# GPRS.net
KiCad netlist of a schematic drawn in Altium Designer
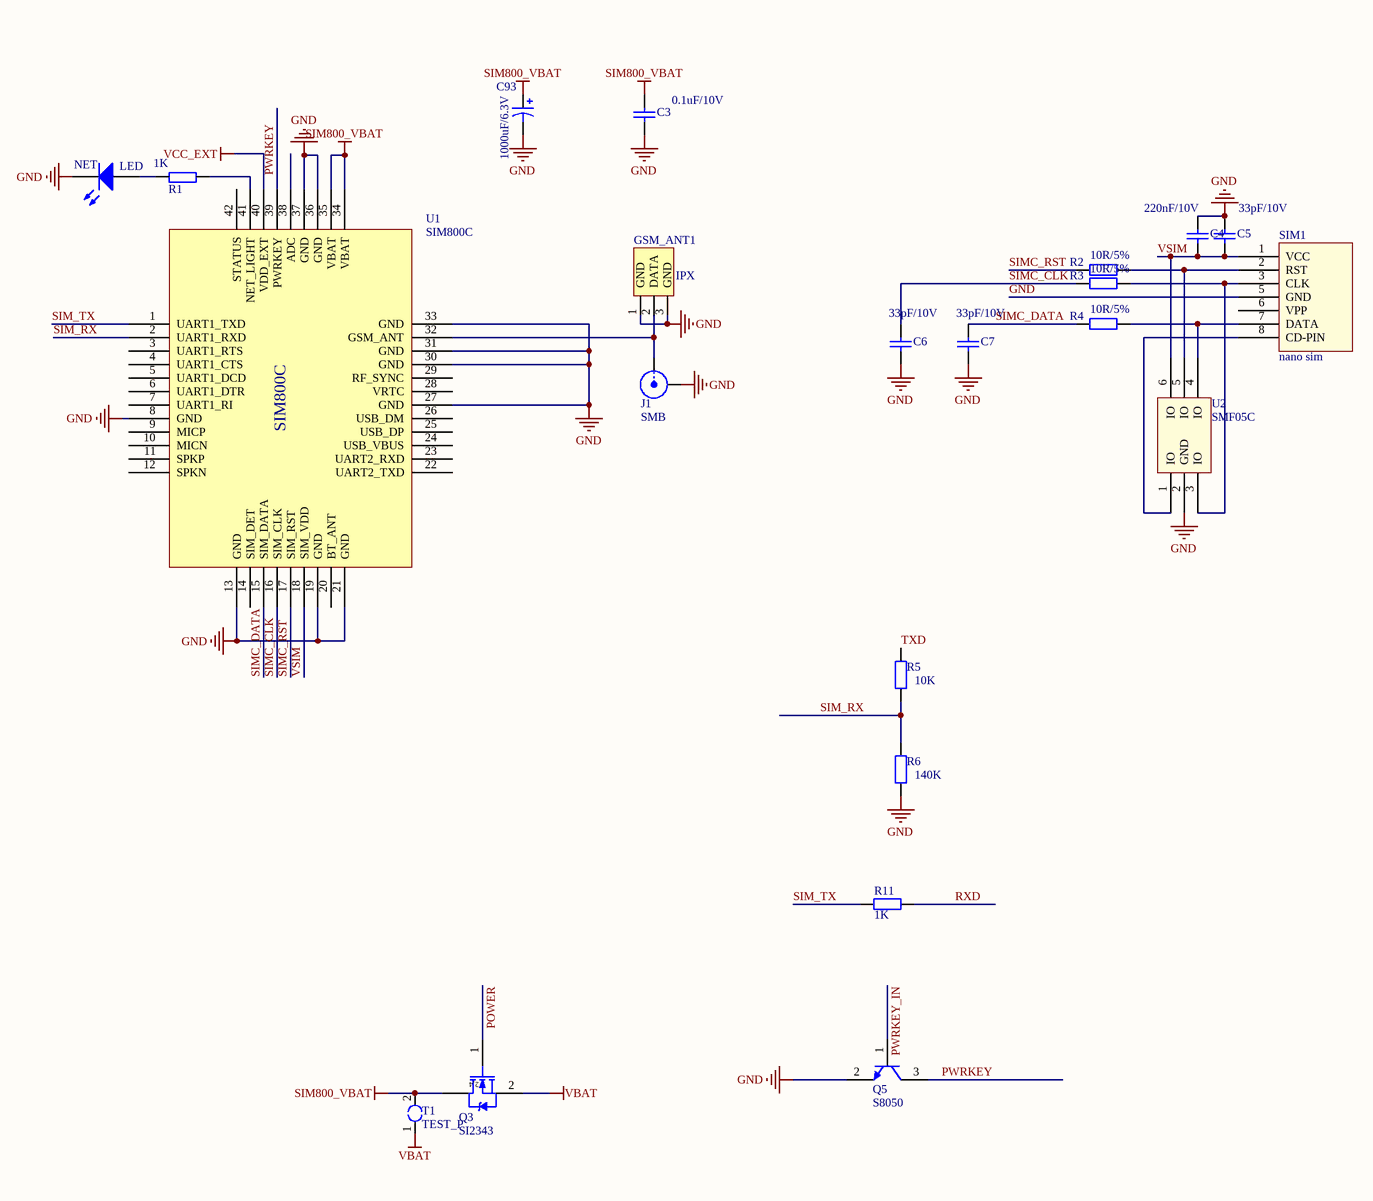
[diagram p0: GPRS.SchDoc]

(export (version "E")
  (design (tool "Eeschema 10.0.6"))
  (components
    (comp (ref "C3")
      (value "0.1uF/10V")
      (footprint "0603C")
      (description "Capacitor")
      (fields (field (name "PUBLISHER") "Altium Limited"))
      (libsource (lib "Miscellaneous Devices") (part "Cap"))
    )
    (comp (ref "C4")
      (value "220nF/10V")
      (footprint "0603C")
      (description "Capacitor")
      (fields (field (name "PUBLISHER") "Altium Limited"))
      (libsource (lib "Miscellaneous Devices") (part "Cap"))
    )
    (comp (ref "C5")
      (value "33pF/10V")
      (footprint "0603C")
      (description "Capacitor")
      (fields (field (name "PUBLISHER") "Altium Limited"))
      (libsource (lib "Miscellaneous Devices") (part "Cap"))
    )
    (comp (ref "C6")
      (value "33pF/10V")
      (footprint "0603C")
      (description "Capacitor")
      (fields (field (name "PUBLISHER") "Altium Limited"))
      (libsource (lib "Miscellaneous Devices") (part "Cap"))
    )
    (comp (ref "C7")
      (value "33pF/10V")
      (footprint "0603C")
      (description "Capacitor")
      (fields (field (name "PUBLISHER") "Altium Limited"))
      (libsource (lib "Miscellaneous Devices") (part "Cap"))
    )
    (comp (ref "C93")
      (value "1000uF/6.3V")
      (footprint "7343")
      (description "Polarized Capacitor (Radial)")
      (fields (field (name "PUBLISHER") "Altium Limited"))
      (libsource (lib "Miscellaneous Devices") (part "Cap Pol1"))
    )
    (comp (ref "GSM_ANT1")
      (value "IPX")
      (footprint "IPX")
      (description "IPEX座")
      (libsource (lib "SIM800C 原理图库") (part "IPEX"))
    )
    (comp (ref "J1")
      (value "SMB")
      (footprint "SMA END LAUNCH JACK RECEPTACLE SHORT")
      (description "SMB Straight Connector")
      (fields (field (name "PUBLISHER") "Altium Limited"))
      (libsource (lib "SIM800C 原理图库") (part "SMB"))
    )
    (comp (ref "NET")
      (value "LED")
      (footprint "0603LED")
      (description "Typical RED, GREEN, YELLOW, AMBER GaAs LED")
      (fields (field (name "PUBLISHER") "Altium Limited"))
      (libsource (lib "SIM800C 原理图库") (part "LED2"))
    )
    (comp (ref "Q3")
      (value "SI2343")
      (footprint "SOT23-3")
      (description "BUK92150-55A")
      (fields (field (name "PUBLISHER") "Altium Limited"))
      (libsource (lib "Schlib1") (part "BUK92150-55A"))
    )
    (comp (ref "Q5") (value "S8050") (footprint "SOT23-3") (libsource (lib "Schlib1") (part "NPN")))
    (comp (ref "R1") (value "1K") (footprint "0603r") (libsource (lib "SIM800C 原理图库") (part "R")))
    (comp (ref "R2")
      (value "10R/5%")
      (footprint "0603R")
      (description "Resistor")
      (fields (field (name "PUBLISHER") "Altium Limited"))
      (libsource (lib "") (part "Res2_1"))
    )
    (comp (ref "R3")
      (value "10R/5%")
      (footprint "0603R")
      (description "Resistor")
      (fields (field (name "PUBLISHER") "Altium Limited"))
      (libsource (lib "") (part "Res2_1"))
    )
    (comp (ref "R4")
      (value "10R/5%")
      (footprint "0603R")
      (description "Resistor")
      (fields (field (name "PUBLISHER") "Altium Limited"))
      (libsource (lib "") (part "Res2_1"))
    )
    (comp (ref "R5")
      (value "10K")
      (footprint "0603R")
      (description "Resistor")
      (fields (field (name "PUBLISHER") "Altium Limited"))
      (libsource (lib "") (part "Res2_2"))
    )
    (comp (ref "R6")
      (value "140K")
      (footprint "0603R")
      (description "Resistor")
      (fields (field (name "PUBLISHER") "Altium Limited"))
      (libsource (lib "") (part "Res2_2"))
    )
    (comp (ref "R11")
      (value "1K")
      (footprint "0603R")
      (description "Resistor")
      (fields (field (name "PUBLISHER") "Altium Limited"))
      (libsource (lib "Miscellaneous Devices") (part "Res2"))
    )
    (comp (ref "SIM1") (value "nano sim") (footprint "Nano SIM") (libsource (lib "lm") (part "nano sim")))
    (comp (ref "T1")
      (value "TEST_P")
      (footprint "TEST_P")
      (libsource (lib "Schlib_20110825") (part "TEST_P"))
    )
    (comp (ref "U1")
      (value "SIM800C")
      (footprint "SIM800C")
      (libsource (lib "SIM800C 原理图库") (part "SIM800C"))
    )
    (comp (ref "U2") (value "SMF05C") (footprint "SC70-6L") (libsource (lib "lm") (part "SMF05C")))
  )
  (nets
    (net (code "1") (name "/POWER") (class "Default")
      (node (ref "Q3") (pin "1") (pinfunction "G_1") (pintype "passive"))
    )
    (net (code "2") (name "/PWRKEY") (class "Default")
      (node (ref "Q5") (pin "3") (pinfunction "C_3") (pintype "passive"))
      (node (ref "U1") (pin "39") (pinfunction "PWRKEY_39") (pintype "passive"))
    )
    (net (code "3") (name "/PWRKEY_IN") (class "Default")
      (node (ref "Q5") (pin "1") (pinfunction "B_1") (pintype "passive"))
    )
    (net (code "4") (name "/RXD") (class "Default")
      (node (ref "R11") (pin "2") (pinfunction "2_2") (pintype "passive"))
    )
    (net (code "5") (name "/SIMC_CLK") (class "Default")
      (node (ref "C6") (pin "1") (pinfunction "1_1") (pintype "passive"))
      (node (ref "R3") (pin "2") (pinfunction "2_2") (pintype "passive"))
      (node (ref "U1") (pin "16") (pinfunction "SIM_CLK_16") (pintype "passive"))
    )
    (net (code "6") (name "/SIMC_DATA") (class "Default")
      (node (ref "C7") (pin "1") (pinfunction "1_1") (pintype "passive"))
      (node (ref "R4") (pin "2") (pinfunction "2_2") (pintype "passive"))
      (node (ref "U1") (pin "15") (pinfunction "SIM_DATA_15") (pintype "passive"))
    )
    (net (code "7") (name "/SIMC_RST") (class "Default")
      (node (ref "R2") (pin "2") (pinfunction "2_2") (pintype "passive"))
      (node (ref "U1") (pin "17") (pinfunction "SIM_RST_17") (pintype "passive"))
    )
    (net (code "8") (name "/SIM_RX") (class "Default")
      (node (ref "R5") (pin "2") (pinfunction "2_2") (pintype "passive"))
      (node (ref "R6") (pin "1") (pinfunction "1_1") (pintype "passive"))
      (node (ref "U1") (pin "2") (pinfunction "UART1_RXD_2") (pintype "passive"))
    )
    (net (code "9") (name "/SIM_TX") (class "Default")
      (node (ref "R11") (pin "1") (pinfunction "1_1") (pintype "passive"))
      (node (ref "U1") (pin "1") (pinfunction "UART1_TXD_1") (pintype "passive"))
    )
    (net (code "10") (name "/TXD") (class "Default")
      (node (ref "R5") (pin "1") (pinfunction "1_1") (pintype "passive"))
    )
    (net (code "11") (name "/VSIM") (class "Default")
      (node (ref "C4") (pin "2") (pinfunction "2_2") (pintype "passive"))
      (node (ref "C5") (pin "2") (pinfunction "2_2") (pintype "passive"))
      (node (ref "SIM1") (pin "1") (pinfunction "VCC_1") (pintype "passive"))
      (node (ref "U1") (pin "18") (pinfunction "SIM_VDD_18") (pintype "passive"))
      (node (ref "U2") (pin "6") (pinfunction "IO_6") (pintype "passive"))
    )
    (net (code "12") (name "GND") (class "Default")
      (node (ref "C3") (pin "2") (pinfunction "2_2") (pintype "passive"))
      (node (ref "C4") (pin "1") (pinfunction "1_1") (pintype "passive"))
      (node (ref "C5") (pin "1") (pinfunction "1_1") (pintype "passive"))
      (node (ref "C6") (pin "2") (pinfunction "2_2") (pintype "passive"))
      (node (ref "C7") (pin "2") (pinfunction "2_2") (pintype "passive"))
      (node (ref "C93") (pin "2") (pinfunction "2_2") (pintype "passive"))
      (node (ref "GSM_ANT1") (pin "1") (pinfunction "GND_1") (pintype "passive"))
      (node (ref "GSM_ANT1") (pin "3") (pinfunction "GND_3") (pintype "passive"))
      (node (ref "J1") (pin "2") (pinfunction "Y_2") (pintype "passive"))
      (node (ref "NET") (pin "2") (pinfunction "K_2") (pintype "passive"))
      (node (ref "Q5") (pin "2") (pinfunction "E_2") (pintype "passive"))
      (node (ref "R6") (pin "2") (pinfunction "2_2") (pintype "passive"))
      (node (ref "SIM1") (pin "5") (pinfunction "GND_5") (pintype "passive"))
      (node (ref "U1") (pin "13") (pinfunction "GND_13") (pintype "passive"))
      (node (ref "U1") (pin "19") (pinfunction "GND_19") (pintype "passive"))
      (node (ref "U1") (pin "21") (pinfunction "GND_21") (pintype "passive"))
      (node (ref "U1") (pin "27") (pinfunction "GND_27") (pintype "passive"))
      (node (ref "U1") (pin "30") (pinfunction "GND_30") (pintype "passive"))
      (node (ref "U1") (pin "31") (pinfunction "GND_31") (pintype "passive"))
      (node (ref "U1") (pin "33") (pinfunction "GND_33") (pintype "passive"))
      (node (ref "U1") (pin "36") (pinfunction "GND_36") (pintype "passive"))
      (node (ref "U1") (pin "37") (pinfunction "GND_37") (pintype "passive"))
      (node (ref "U1") (pin "8") (pinfunction "GND_8") (pintype "passive"))
      (node (ref "U2") (pin "2") (pinfunction "GND_2") (pintype "passive"))
    )
    (net (code "13") (name "Net-(GSM_ANT1-DATA)") (class "Default")
      (node (ref "GSM_ANT1") (pin "2") (pinfunction "DATA_2") (pintype "passive"))
      (node (ref "J1") (pin "1") (pinfunction "X_1") (pintype "passive"))
      (node (ref "U1") (pin "32") (pinfunction "GSM_ANT_32") (pintype "passive"))
    )
    (net (code "14") (name "Net-(NET-A)") (class "Default")
      (node (ref "NET") (pin "1") (pinfunction "A_1") (pintype "passive"))
      (node (ref "R1") (pin "1") (pintype "passive"))
    )
    (net (code "15") (name "Net-(SIM1-CD-PIN)") (class "Default")
      (node (ref "SIM1") (pin "8") (pinfunction "CD-PIN_8") (pintype "passive"))
      (node (ref "U2") (pin "1") (pinfunction "IO_1") (pintype "passive"))
    )
    (net (code "16") (name "Net-(SIM1-CLK)") (class "Default")
      (node (ref "R3") (pin "1") (pinfunction "1_1") (pintype "passive"))
      (node (ref "SIM1") (pin "3") (pinfunction "CLK_3") (pintype "passive"))
      (node (ref "U2") (pin "3") (pinfunction "IO_3") (pintype "passive"))
    )
    (net (code "17") (name "Net-(SIM1-DATA)") (class "Default")
      (node (ref "R4") (pin "1") (pinfunction "1_1") (pintype "passive"))
      (node (ref "SIM1") (pin "7") (pinfunction "DATA_7") (pintype "passive"))
      (node (ref "U2") (pin "4") (pinfunction "IO_4") (pintype "passive"))
    )
    (net (code "18") (name "Net-(SIM1-RST)") (class "Default")
      (node (ref "R2") (pin "1") (pinfunction "1_1") (pintype "passive"))
      (node (ref "SIM1") (pin "2") (pinfunction "RST_2") (pintype "passive"))
      (node (ref "U2") (pin "5") (pinfunction "IO_5") (pintype "passive"))
    )
    (net (code "19") (name "Net-(U1-NET_LIGHT)") (class "Default")
      (node (ref "R1") (pin "2") (pintype "passive"))
      (node (ref "U1") (pin "41") (pinfunction "NET_LIGHT_41") (pintype "passive"))
    )
    (net (code "20") (name "SIM800_VBAT") (class "Default")
      (node (ref "C3") (pin "1") (pinfunction "1_1") (pintype "passive"))
      (node (ref "C93") (pin "1") (pinfunction "1_1") (pintype "passive"))
      (node (ref "Q3") (pin "3") (pinfunction "D_3") (pintype "passive"))
      (node (ref "T1") (pin "2") (pinfunction "2_2") (pintype "passive"))
      (node (ref "U1") (pin "34") (pinfunction "VBAT_34") (pintype "passive"))
      (node (ref "U1") (pin "35") (pinfunction "VBAT_35") (pintype "passive"))
    )
    (net (code "21") (name "VBAT") (class "Default")
      (node (ref "Q3") (pin "2") (pinfunction "S_2") (pintype "passive"))
      (node (ref "T1") (pin "1") (pinfunction "1_1") (pintype "passive"))
    )
    (net (code "22") (name "VCC_EXT") (class "Default")
      (node (ref "U1") (pin "40") (pinfunction "VDD_EXT_40") (pintype "passive"))
    )
    (net (code "23") (name "unconnected-(SIM1-VPP-Pad6)") (class "Default")
      (node (ref "SIM1") (pin "6") (pinfunction "VPP_6") (pintype "passive"))
    )
    (net (code "24") (name "unconnected-(U1-ADC-Pad38)") (class "Default")
      (node (ref "U1") (pin "38") (pinfunction "ADC_38") (pintype "passive"))
    )
    (net (code "25") (name "unconnected-(U1-BT_ANT-Pad20)") (class "Default")
      (node (ref "U1") (pin "20") (pinfunction "BT_ANT_20") (pintype "passive"))
    )
    (net (code "26") (name "unconnected-(U1-MICN-Pad10)") (class "Default")
      (node (ref "U1") (pin "10") (pinfunction "MICN_10") (pintype "passive"))
    )
    (net (code "27") (name "unconnected-(U1-MICP-Pad9)") (class "Default")
      (node (ref "U1") (pin "9") (pinfunction "MICP_9") (pintype "passive"))
    )
    (net (code "28") (name "unconnected-(U1-RF_SYNC-Pad29)") (class "Default")
      (node (ref "U1") (pin "29") (pinfunction "RF_SYNC_29") (pintype "passive"))
    )
    (net (code "29") (name "unconnected-(U1-SIM_DET-Pad14)") (class "Default")
      (node (ref "U1") (pin "14") (pinfunction "SIM_DET_14") (pintype "passive"))
    )
    (net (code "30") (name "unconnected-(U1-SPKN-Pad12)") (class "Default")
      (node (ref "U1") (pin "12") (pinfunction "SPKN_12") (pintype "passive"))
    )
    (net (code "31") (name "unconnected-(U1-SPKP-Pad11)") (class "Default")
      (node (ref "U1") (pin "11") (pinfunction "SPKP_11") (pintype "passive"))
    )
    (net (code "32") (name "unconnected-(U1-STATUS-Pad42)") (class "Default")
      (node (ref "U1") (pin "42") (pinfunction "STATUS_42") (pintype "passive"))
    )
    (net (code "33") (name "unconnected-(U1-UART1_CTS-Pad4)") (class "Default")
      (node (ref "U1") (pin "4") (pinfunction "UART1_CTS_4") (pintype "passive"))
    )
    (net (code "34") (name "unconnected-(U1-UART1_DCD-Pad5)") (class "Default")
      (node (ref "U1") (pin "5") (pinfunction "UART1_DCD_5") (pintype "passive"))
    )
    (net (code "35") (name "unconnected-(U1-UART1_DTR-Pad6)") (class "Default")
      (node (ref "U1") (pin "6") (pinfunction "UART1_DTR_6") (pintype "passive"))
    )
    (net (code "36") (name "unconnected-(U1-UART1_RI-Pad7)") (class "Default")
      (node (ref "U1") (pin "7") (pinfunction "UART1_RI_7") (pintype "passive"))
    )
    (net (code "37") (name "unconnected-(U1-UART1_RTS-Pad3)") (class "Default")
      (node (ref "U1") (pin "3") (pinfunction "UART1_RTS_3") (pintype "passive"))
    )
    (net (code "38") (name "unconnected-(U1-UART2_RXD-Pad23)") (class "Default")
      (node (ref "U1") (pin "23") (pinfunction "UART2_RXD_23") (pintype "passive"))
    )
    (net (code "39") (name "unconnected-(U1-UART2_TXD-Pad22)") (class "Default")
      (node (ref "U1") (pin "22") (pinfunction "UART2_TXD_22") (pintype "passive"))
    )
    (net (code "40") (name "unconnected-(U1-USB_DM-Pad26)") (class "Default")
      (node (ref "U1") (pin "26") (pinfunction "USB_DM_26") (pintype "passive"))
    )
    (net (code "41") (name "unconnected-(U1-USB_DP-Pad25)") (class "Default")
      (node (ref "U1") (pin "25") (pinfunction "USB_DP_25") (pintype "passive"))
    )
    (net (code "42") (name "unconnected-(U1-USB_VBUS-Pad24)") (class "Default")
      (node (ref "U1") (pin "24") (pinfunction "USB_VBUS_24") (pintype "passive"))
    )
    (net (code "43") (name "unconnected-(U1-VRTC-Pad28)") (class "Default")
      (node (ref "U1") (pin "28") (pinfunction "VRTC_28") (pintype "passive"))
    )
  )
)
